# CD_full_schematic.net
KiCad netlist of a schematic drawn in EAGLE
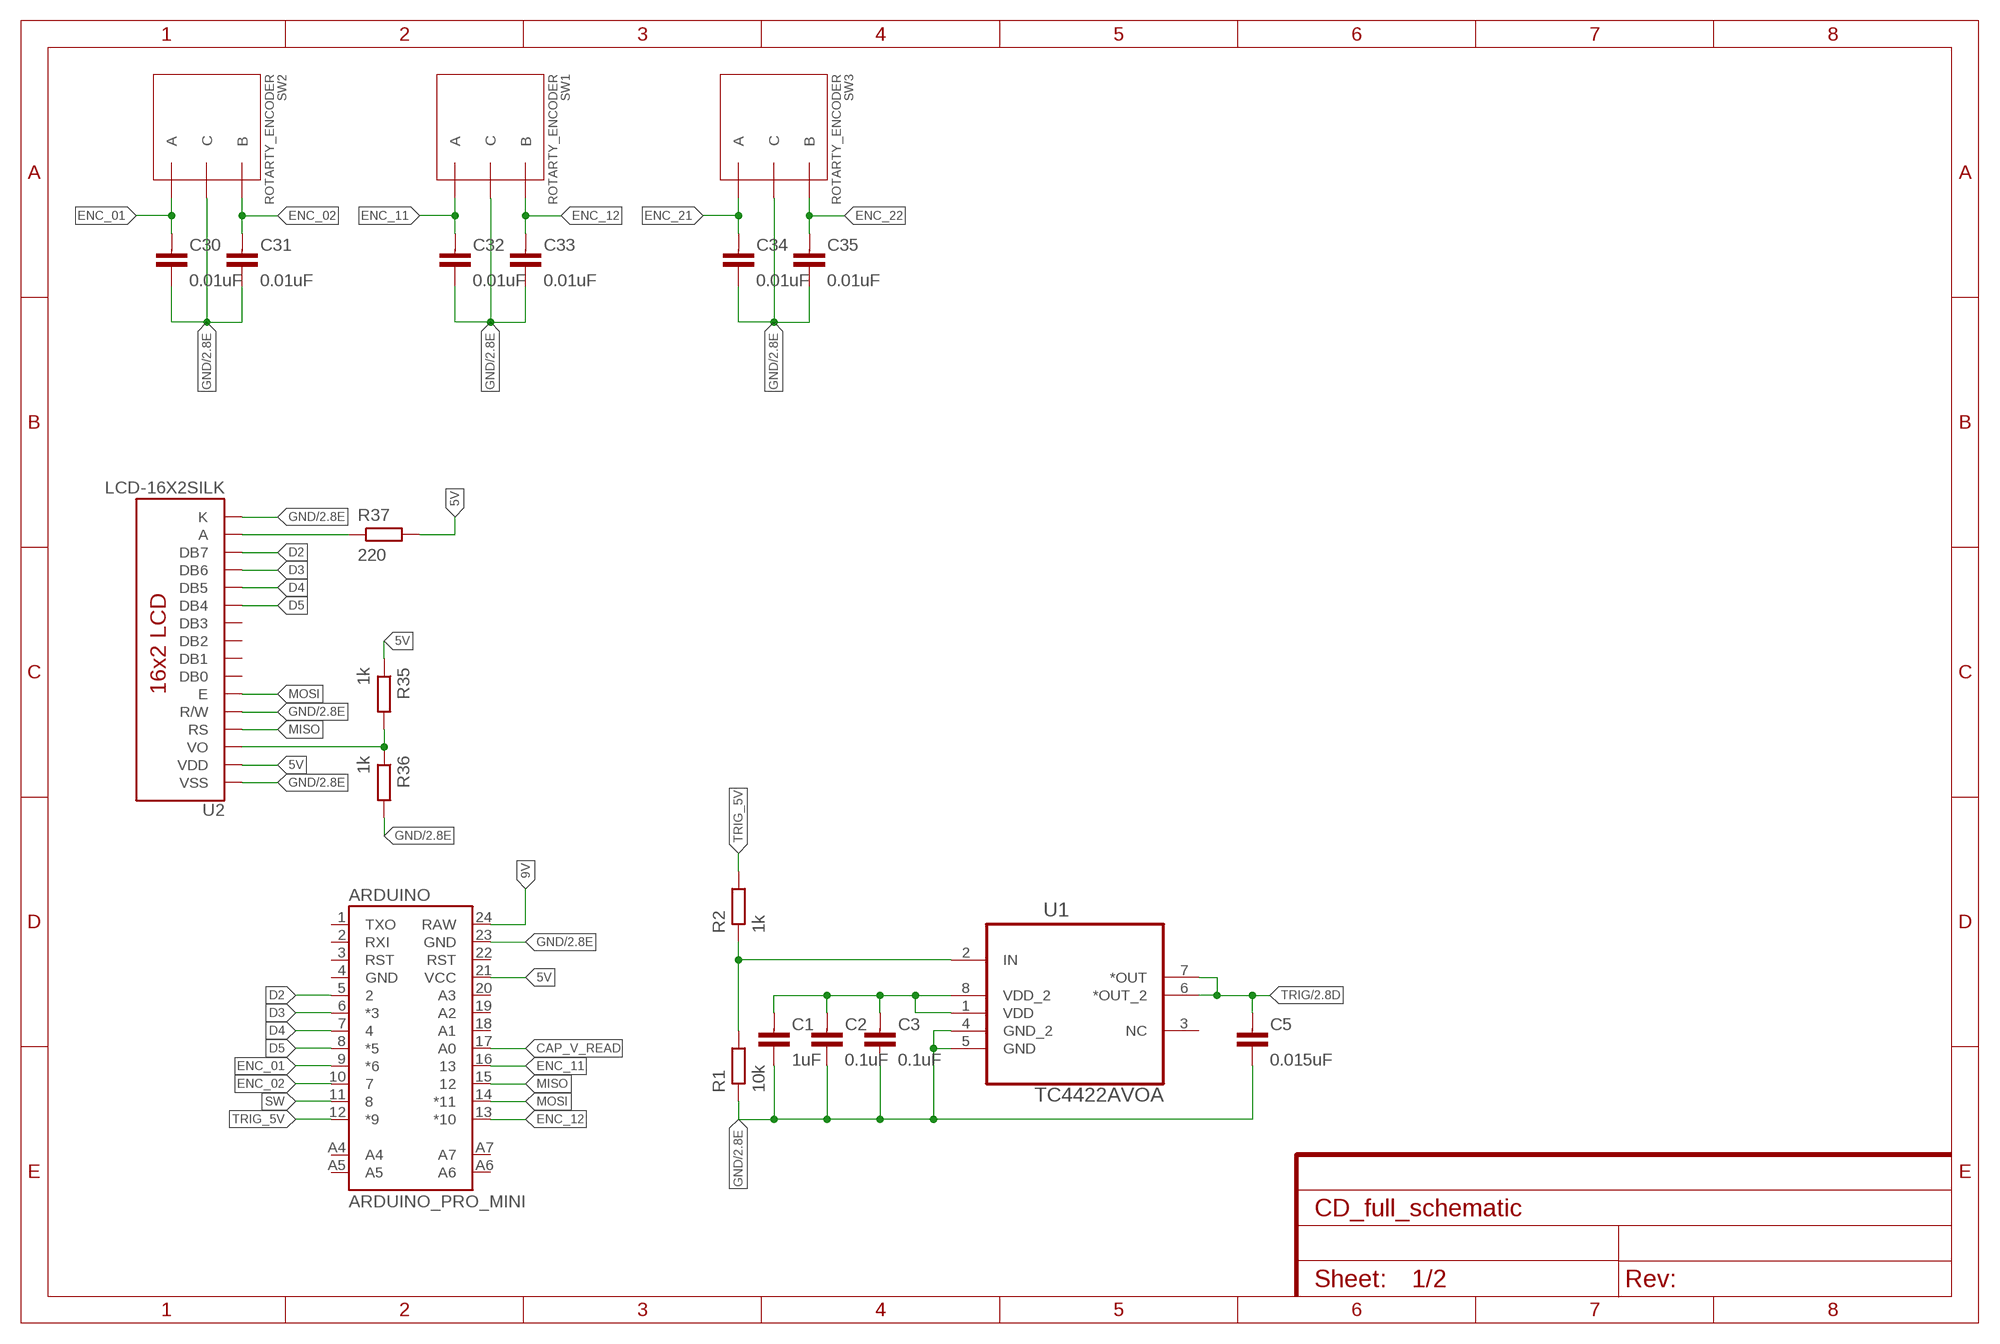
[diagram p0: schematic, sheet 1]
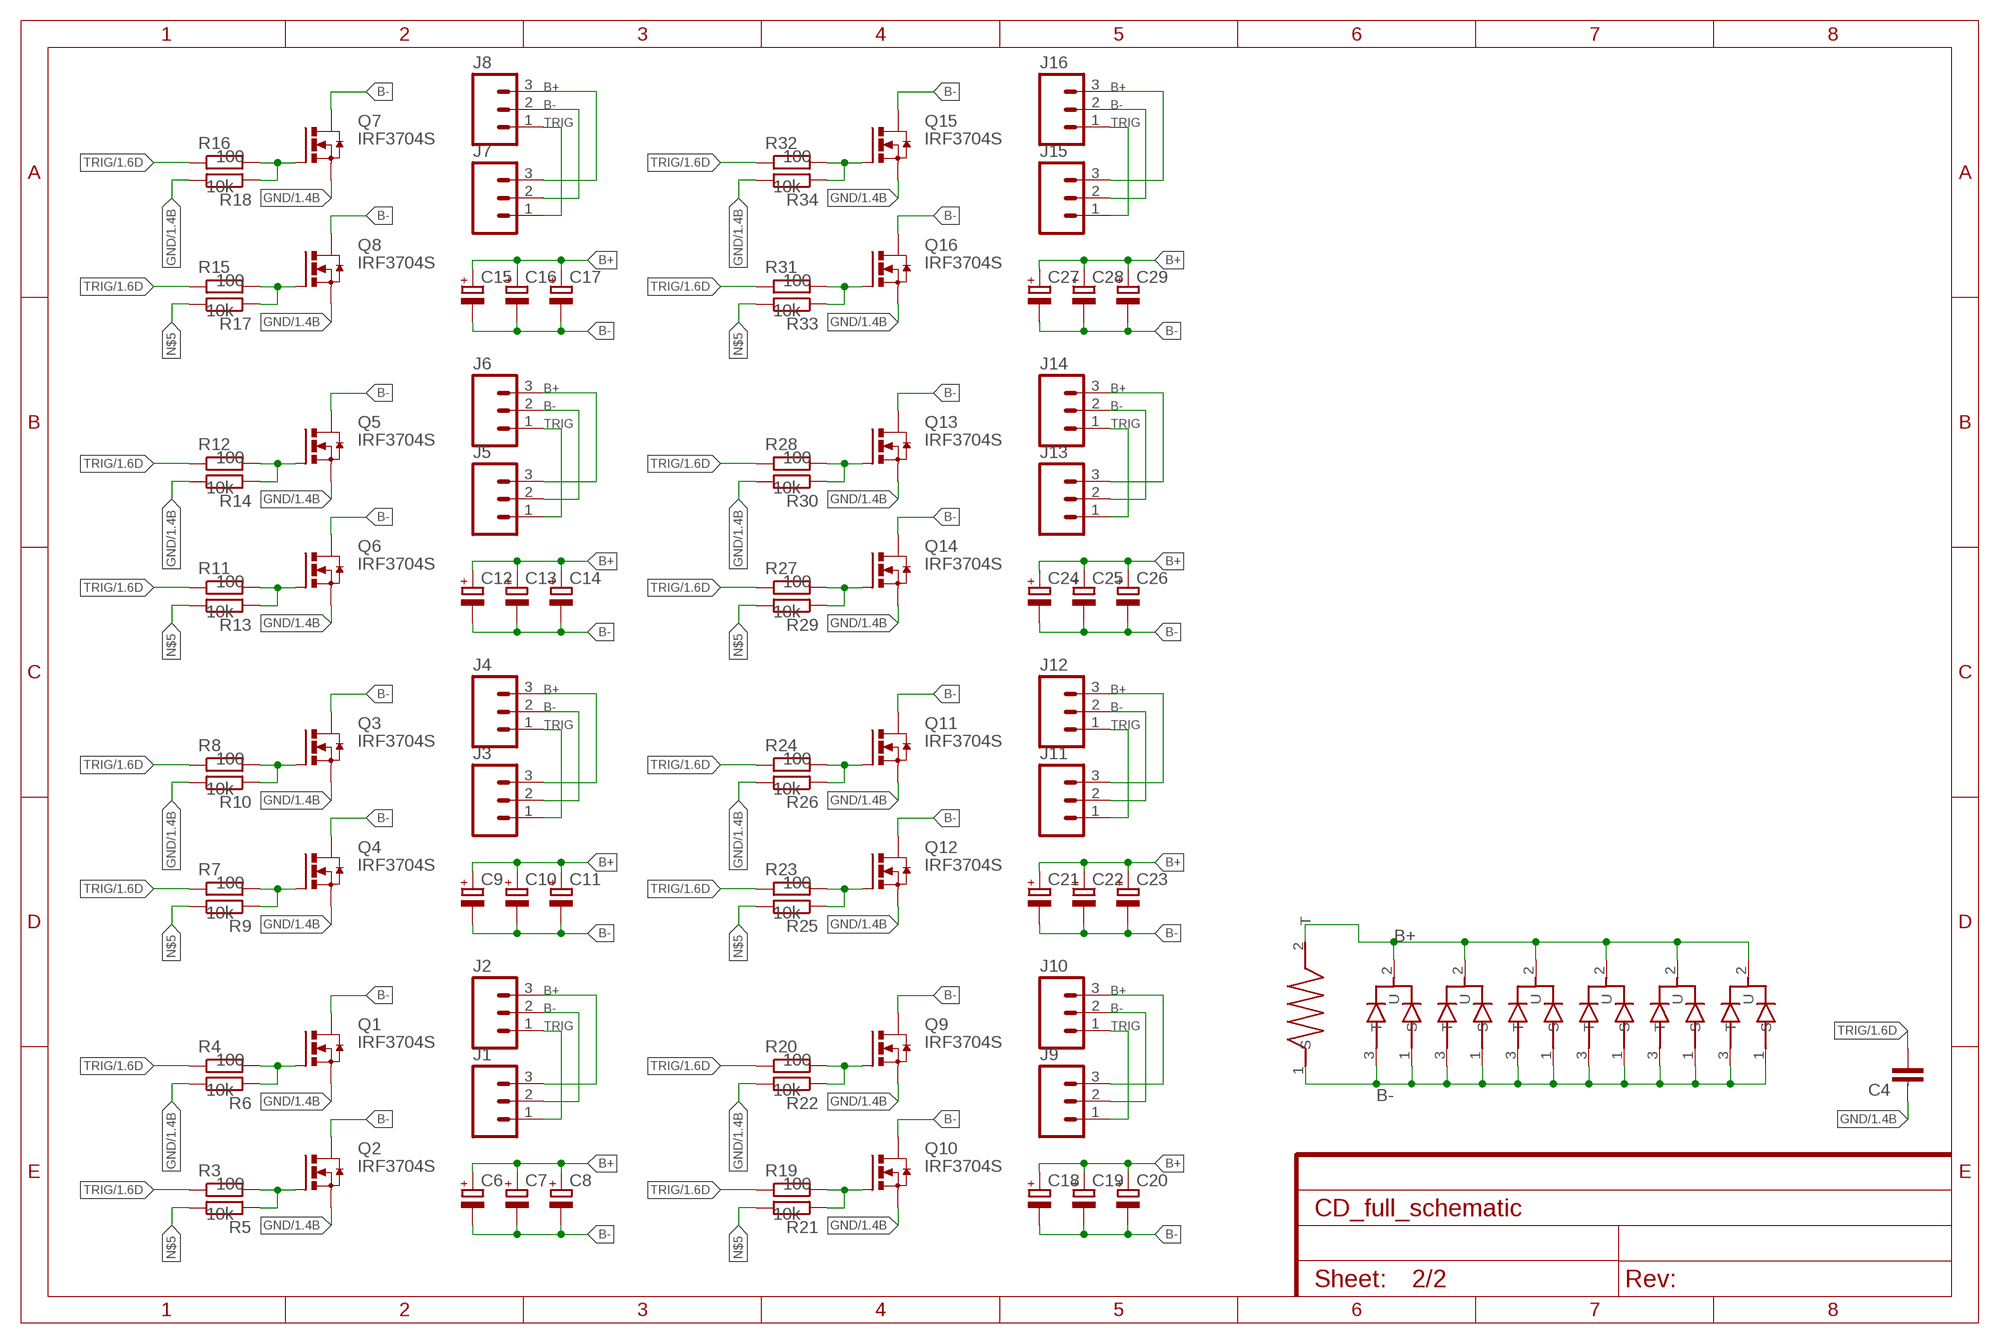
[diagram p1: schematic, sheet 2]

(export (version "E")
  (design (tool "Eeschema 10.0.6"))
  (components
    (comp (ref "ARDUINO")
      (value "ARDUINO_PRO_MINI")
      (footprint "eagle-import:ARDUINO_PRO_MINI")
      (libsource (lib "eagle-import") (part "ARDUINO_PRO_MINI"))
    )
    (comp (ref "C1")
      (value "1uF")
      (footprint "eagle-import:C0805-N")
      (libsource (lib "eagle-import") (part "CAPACITOR0805-N"))
    )
    (comp (ref "C2")
      (value "0.1uF")
      (footprint "eagle-import:C0603-N")
      (libsource (lib "eagle-import") (part "CAPACITOR0603-N"))
    )
    (comp (ref "C3")
      (value "0.1uF")
      (footprint "eagle-import:C0603-N")
      (libsource (lib "eagle-import") (part "CAPACITOR0603-N"))
    )
    (comp (ref "C5")
      (value "0.015uF")
      (footprint "eagle-import:C0603-N")
      (libsource (lib "eagle-import") (part "CAPACITOR0603-N"))
    )
    (comp (ref "C30")
      (value "0.01uF")
      (footprint "eagle-import:C0603-N")
      (libsource (lib "eagle-import") (part "CAPACITOR0603-N"))
    )
    (comp (ref "C31")
      (value "0.01uF")
      (footprint "eagle-import:C0603-N")
      (libsource (lib "eagle-import") (part "CAPACITOR0603-N"))
    )
    (comp (ref "C32")
      (value "0.01uF")
      (footprint "eagle-import:C0603-N")
      (libsource (lib "eagle-import") (part "CAPACITOR0603-N"))
    )
    (comp (ref "C33")
      (value "0.01uF")
      (footprint "eagle-import:C0603-N")
      (libsource (lib "eagle-import") (part "CAPACITOR0603-N"))
    )
    (comp (ref "C34")
      (value "0.01uF")
      (footprint "eagle-import:C0603-N")
      (libsource (lib "eagle-import") (part "CAPACITOR0603-N"))
    )
    (comp (ref "C35")
      (value "0.01uF")
      (footprint "eagle-import:C0603-N")
      (libsource (lib "eagle-import") (part "CAPACITOR0603-N"))
    )
    (comp (ref "R1")
      (value "10k")
      (footprint "eagle-import:R0603-N")
      (libsource (lib "eagle-import") (part "RESISTOR0603-N"))
    )
    (comp (ref "R2")
      (value "1k")
      (footprint "eagle-import:R0603-N")
      (libsource (lib "eagle-import") (part "RESISTOR0603-N"))
    )
    (comp (ref "R35")
      (value "1k")
      (footprint "eagle-import:R0603-N")
      (libsource (lib "eagle-import") (part "RESISTOR0603-N"))
    )
    (comp (ref "R36")
      (value "1k")
      (footprint "eagle-import:R0603-N")
      (libsource (lib "eagle-import") (part "RESISTOR0603-N"))
    )
    (comp (ref "R37")
      (value "220")
      (footprint "eagle-import:R0603-N")
      (libsource (lib "eagle-import") (part "RESISTOR0603-N"))
    )
    (comp (ref "SW1")
      (value "ROTARTY_ENCODER")
      (footprint "eagle-import:ROTARY_ENC_PLAIN")
      (libsource (lib "eagle-import") (part "ROTARTY_ENCODER"))
    )
    (comp (ref "SW2")
      (value "ROTARTY_ENCODER")
      (footprint "eagle-import:ROTARY_ENC_PLAIN")
      (libsource (lib "eagle-import") (part "ROTARTY_ENCODER"))
    )
    (comp (ref "SW3")
      (value "ROTARTY_ENCODER")
      (footprint "eagle-import:ROTARY_ENC_PLAIN")
      (libsource (lib "eagle-import") (part "ROTARTY_ENCODER"))
    )
    (comp (ref "U1")
      (value "TC4422AVOA")
      (footprint "eagle-import:SOIC127P600X175-8N")
      (libsource (lib "eagle-import") (part "TC4422AVOA"))
    )
    (comp (ref "U2")
      (value "LCD-16X2SILK")
      (footprint "eagle-import:LCD-16X2")
      (libsource (lib "eagle-import") (part "LCD-16X2SILK"))
    )
    (comp (ref "C4")
      (value "CAPACITOR0603-N")
      (footprint "eagle-import:C0603-N")
      (libsource (lib "eagle-import") (part "CAPACITOR0603-N"))
    )
    (comp (ref "C6")
      (value "CPOL-EUE10-35")
      (footprint "eagle-import:EB35D")
      (libsource (lib "eagle-import") (part "CPOL-EUE10-35"))
    )
    (comp (ref "C7")
      (value "CPOL-EUE10-35")
      (footprint "eagle-import:EB35D")
      (libsource (lib "eagle-import") (part "CPOL-EUE10-35"))
    )
    (comp (ref "C8")
      (value "CPOL-EUE10-35")
      (footprint "eagle-import:EB35D")
      (libsource (lib "eagle-import") (part "CPOL-EUE10-35"))
    )
    (comp (ref "C9")
      (value "CPOL-EUE10-35")
      (footprint "eagle-import:EB35D")
      (libsource (lib "eagle-import") (part "CPOL-EUE10-35"))
    )
    (comp (ref "C10")
      (value "CPOL-EUE10-35")
      (footprint "eagle-import:EB35D")
      (libsource (lib "eagle-import") (part "CPOL-EUE10-35"))
    )
    (comp (ref "C11")
      (value "CPOL-EUE10-35")
      (footprint "eagle-import:EB35D")
      (libsource (lib "eagle-import") (part "CPOL-EUE10-35"))
    )
    (comp (ref "C12")
      (value "CPOL-EUE10-35")
      (footprint "eagle-import:EB35D")
      (libsource (lib "eagle-import") (part "CPOL-EUE10-35"))
    )
    (comp (ref "C13")
      (value "CPOL-EUE10-35")
      (footprint "eagle-import:EB35D")
      (libsource (lib "eagle-import") (part "CPOL-EUE10-35"))
    )
    (comp (ref "C14")
      (value "CPOL-EUE10-35")
      (footprint "eagle-import:EB35D")
      (libsource (lib "eagle-import") (part "CPOL-EUE10-35"))
    )
    (comp (ref "C15")
      (value "CPOL-EUE10-35")
      (footprint "eagle-import:EB35D")
      (libsource (lib "eagle-import") (part "CPOL-EUE10-35"))
    )
    (comp (ref "C16")
      (value "CPOL-EUE10-35")
      (footprint "eagle-import:EB35D")
      (libsource (lib "eagle-import") (part "CPOL-EUE10-35"))
    )
    (comp (ref "C17")
      (value "CPOL-EUE10-35")
      (footprint "eagle-import:EB35D")
      (libsource (lib "eagle-import") (part "CPOL-EUE10-35"))
    )
    (comp (ref "C18")
      (value "CPOL-EUE10-35")
      (footprint "eagle-import:EB35D")
      (libsource (lib "eagle-import") (part "CPOL-EUE10-35"))
    )
    (comp (ref "C19")
      (value "CPOL-EUE10-35")
      (footprint "eagle-import:EB35D")
      (libsource (lib "eagle-import") (part "CPOL-EUE10-35"))
    )
    (comp (ref "C20")
      (value "CPOL-EUE10-35")
      (footprint "eagle-import:EB35D")
      (libsource (lib "eagle-import") (part "CPOL-EUE10-35"))
    )
    (comp (ref "C21")
      (value "CPOL-EUE10-35")
      (footprint "eagle-import:EB35D")
      (libsource (lib "eagle-import") (part "CPOL-EUE10-35"))
    )
    (comp (ref "C22")
      (value "CPOL-EUE10-35")
      (footprint "eagle-import:EB35D")
      (libsource (lib "eagle-import") (part "CPOL-EUE10-35"))
    )
    (comp (ref "C23")
      (value "CPOL-EUE10-35")
      (footprint "eagle-import:EB35D")
      (libsource (lib "eagle-import") (part "CPOL-EUE10-35"))
    )
    (comp (ref "C24")
      (value "CPOL-EUE10-35")
      (footprint "eagle-import:EB35D")
      (libsource (lib "eagle-import") (part "CPOL-EUE10-35"))
    )
    (comp (ref "C25")
      (value "CPOL-EUE10-35")
      (footprint "eagle-import:EB35D")
      (libsource (lib "eagle-import") (part "CPOL-EUE10-35"))
    )
    (comp (ref "C26")
      (value "CPOL-EUE10-35")
      (footprint "eagle-import:EB35D")
      (libsource (lib "eagle-import") (part "CPOL-EUE10-35"))
    )
    (comp (ref "C27")
      (value "CPOL-EUE10-35")
      (footprint "eagle-import:EB35D")
      (libsource (lib "eagle-import") (part "CPOL-EUE10-35"))
    )
    (comp (ref "C28")
      (value "CPOL-EUE10-35")
      (footprint "eagle-import:EB35D")
      (libsource (lib "eagle-import") (part "CPOL-EUE10-35"))
    )
    (comp (ref "C29")
      (value "CPOL-EUE10-35")
      (footprint "eagle-import:EB35D")
      (libsource (lib "eagle-import") (part "CPOL-EUE10-35"))
    )
    (comp (ref "J1")
      (value "M03PTH")
      (footprint "eagle-import:1X03")
      (libsource (lib "eagle-import") (part "M03PTH"))
    )
    (comp (ref "J2")
      (value "M03PTH")
      (footprint "eagle-import:1X03")
      (libsource (lib "eagle-import") (part "M03PTH"))
    )
    (comp (ref "J3")
      (value "M03PTH")
      (footprint "eagle-import:1X03")
      (libsource (lib "eagle-import") (part "M03PTH"))
    )
    (comp (ref "J4")
      (value "M03PTH")
      (footprint "eagle-import:1X03")
      (libsource (lib "eagle-import") (part "M03PTH"))
    )
    (comp (ref "J5")
      (value "M03PTH")
      (footprint "eagle-import:1X03")
      (libsource (lib "eagle-import") (part "M03PTH"))
    )
    (comp (ref "J6")
      (value "M03PTH")
      (footprint "eagle-import:1X03")
      (libsource (lib "eagle-import") (part "M03PTH"))
    )
    (comp (ref "J7")
      (value "M03PTH")
      (footprint "eagle-import:1X03")
      (libsource (lib "eagle-import") (part "M03PTH"))
    )
    (comp (ref "J8")
      (value "M03PTH")
      (footprint "eagle-import:1X03")
      (libsource (lib "eagle-import") (part "M03PTH"))
    )
    (comp (ref "J9")
      (value "M03PTH")
      (footprint "eagle-import:1X03")
      (libsource (lib "eagle-import") (part "M03PTH"))
    )
    (comp (ref "J10")
      (value "M03PTH")
      (footprint "eagle-import:1X03")
      (libsource (lib "eagle-import") (part "M03PTH"))
    )
    (comp (ref "J11")
      (value "M03PTH")
      (footprint "eagle-import:1X03")
      (libsource (lib "eagle-import") (part "M03PTH"))
    )
    (comp (ref "J12")
      (value "M03PTH")
      (footprint "eagle-import:1X03")
      (libsource (lib "eagle-import") (part "M03PTH"))
    )
    (comp (ref "J13")
      (value "M03PTH")
      (footprint "eagle-import:1X03")
      (libsource (lib "eagle-import") (part "M03PTH"))
    )
    (comp (ref "J14")
      (value "M03PTH")
      (footprint "eagle-import:1X03")
      (libsource (lib "eagle-import") (part "M03PTH"))
    )
    (comp (ref "J15")
      (value "M03PTH")
      (footprint "eagle-import:1X03")
      (libsource (lib "eagle-import") (part "M03PTH"))
    )
    (comp (ref "J16")
      (value "M03PTH")
      (footprint "eagle-import:1X03")
      (libsource (lib "eagle-import") (part "M03PTH"))
    )
    (comp (ref "Q1")
      (value "IRF3704S")
      (footprint "eagle-import:D2PACK")
      (libsource (lib "eagle-import") (part "IRF3704S"))
    )
    (comp (ref "Q2")
      (value "IRF3704S")
      (footprint "eagle-import:D2PACK")
      (libsource (lib "eagle-import") (part "IRF3704S"))
    )
    (comp (ref "Q3")
      (value "IRF3704S")
      (footprint "eagle-import:D2PACK")
      (libsource (lib "eagle-import") (part "IRF3704S"))
    )
    (comp (ref "Q4")
      (value "IRF3704S")
      (footprint "eagle-import:D2PACK")
      (libsource (lib "eagle-import") (part "IRF3704S"))
    )
    (comp (ref "Q5")
      (value "IRF3704S")
      (footprint "eagle-import:D2PACK")
      (libsource (lib "eagle-import") (part "IRF3704S"))
    )
    (comp (ref "Q6")
      (value "IRF3704S")
      (footprint "eagle-import:D2PACK")
      (libsource (lib "eagle-import") (part "IRF3704S"))
    )
    (comp (ref "Q7")
      (value "IRF3704S")
      (footprint "eagle-import:D2PACK")
      (libsource (lib "eagle-import") (part "IRF3704S"))
    )
    (comp (ref "Q8")
      (value "IRF3704S")
      (footprint "eagle-import:D2PACK")
      (libsource (lib "eagle-import") (part "IRF3704S"))
    )
    (comp (ref "Q9")
      (value "IRF3704S")
      (footprint "eagle-import:D2PACK")
      (libsource (lib "eagle-import") (part "IRF3704S"))
    )
    (comp (ref "Q10")
      (value "IRF3704S")
      (footprint "eagle-import:D2PACK")
      (libsource (lib "eagle-import") (part "IRF3704S"))
    )
    (comp (ref "Q11")
      (value "IRF3704S")
      (footprint "eagle-import:D2PACK")
      (libsource (lib "eagle-import") (part "IRF3704S"))
    )
    (comp (ref "Q12")
      (value "IRF3704S")
      (footprint "eagle-import:D2PACK")
      (libsource (lib "eagle-import") (part "IRF3704S"))
    )
    (comp (ref "Q13")
      (value "IRF3704S")
      (footprint "eagle-import:D2PACK")
      (libsource (lib "eagle-import") (part "IRF3704S"))
    )
    (comp (ref "Q14")
      (value "IRF3704S")
      (footprint "eagle-import:D2PACK")
      (libsource (lib "eagle-import") (part "IRF3704S"))
    )
    (comp (ref "Q15")
      (value "IRF3704S")
      (footprint "eagle-import:D2PACK")
      (libsource (lib "eagle-import") (part "IRF3704S"))
    )
    (comp (ref "Q16")
      (value "IRF3704S")
      (footprint "eagle-import:D2PACK")
      (libsource (lib "eagle-import") (part "IRF3704S"))
    )
    (comp (ref "R3")
      (value "100")
      (footprint "eagle-import:R0603-N")
      (libsource (lib "eagle-import") (part "RESISTOR0603-N"))
    )
    (comp (ref "R4")
      (value "100")
      (footprint "eagle-import:R0603-N")
      (libsource (lib "eagle-import") (part "RESISTOR0603-N"))
    )
    (comp (ref "R5")
      (value "10k")
      (footprint "eagle-import:R0603-N")
      (libsource (lib "eagle-import") (part "RESISTOR0603-N"))
    )
    (comp (ref "R6")
      (value "10k")
      (footprint "eagle-import:R0603-N")
      (libsource (lib "eagle-import") (part "RESISTOR0603-N"))
    )
    (comp (ref "R7")
      (value "100")
      (footprint "eagle-import:R0603-N")
      (libsource (lib "eagle-import") (part "RESISTOR0603-N"))
    )
    (comp (ref "R8")
      (value "100")
      (footprint "eagle-import:R0603-N")
      (libsource (lib "eagle-import") (part "RESISTOR0603-N"))
    )
    (comp (ref "R9")
      (value "10k")
      (footprint "eagle-import:R0603-N")
      (libsource (lib "eagle-import") (part "RESISTOR0603-N"))
    )
    (comp (ref "R10")
      (value "10k")
      (footprint "eagle-import:R0603-N")
      (libsource (lib "eagle-import") (part "RESISTOR0603-N"))
    )
    (comp (ref "R11")
      (value "100")
      (footprint "eagle-import:R0603-N")
      (libsource (lib "eagle-import") (part "RESISTOR0603-N"))
    )
    (comp (ref "R12")
      (value "100")
      (footprint "eagle-import:R0603-N")
      (libsource (lib "eagle-import") (part "RESISTOR0603-N"))
    )
    (comp (ref "R13")
      (value "10k")
      (footprint "eagle-import:R0603-N")
      (libsource (lib "eagle-import") (part "RESISTOR0603-N"))
    )
    (comp (ref "R14")
      (value "10k")
      (footprint "eagle-import:R0603-N")
      (libsource (lib "eagle-import") (part "RESISTOR0603-N"))
    )
    (comp (ref "R15")
      (value "100")
      (footprint "eagle-import:R0603-N")
      (libsource (lib "eagle-import") (part "RESISTOR0603-N"))
    )
    (comp (ref "R16")
      (value "100")
      (footprint "eagle-import:R0603-N")
      (libsource (lib "eagle-import") (part "RESISTOR0603-N"))
    )
    (comp (ref "R17")
      (value "10k")
      (footprint "eagle-import:R0603-N")
      (libsource (lib "eagle-import") (part "RESISTOR0603-N"))
    )
    (comp (ref "R18")
      (value "10k")
      (footprint "eagle-import:R0603-N")
      (libsource (lib "eagle-import") (part "RESISTOR0603-N"))
    )
    (comp (ref "R19")
      (value "100")
      (footprint "eagle-import:R0603-N")
      (libsource (lib "eagle-import") (part "RESISTOR0603-N"))
    )
    (comp (ref "R20")
      (value "100")
      (footprint "eagle-import:R0603-N")
      (libsource (lib "eagle-import") (part "RESISTOR0603-N"))
    )
    (comp (ref "R21")
      (value "10k")
      (footprint "eagle-import:R0603-N")
      (libsource (lib "eagle-import") (part "RESISTOR0603-N"))
    )
    (comp (ref "R22")
      (value "10k")
      (footprint "eagle-import:R0603-N")
      (libsource (lib "eagle-import") (part "RESISTOR0603-N"))
    )
    (comp (ref "R23")
      (value "100")
      (footprint "eagle-import:R0603-N")
      (libsource (lib "eagle-import") (part "RESISTOR0603-N"))
    )
    (comp (ref "R24")
      (value "100")
      (footprint "eagle-import:R0603-N")
      (libsource (lib "eagle-import") (part "RESISTOR0603-N"))
    )
    (comp (ref "R25")
      (value "10k")
      (footprint "eagle-import:R0603-N")
      (libsource (lib "eagle-import") (part "RESISTOR0603-N"))
    )
    (comp (ref "R26")
      (value "10k")
      (footprint "eagle-import:R0603-N")
      (libsource (lib "eagle-import") (part "RESISTOR0603-N"))
    )
    (comp (ref "R27")
      (value "100")
      (footprint "eagle-import:R0603-N")
      (libsource (lib "eagle-import") (part "RESISTOR0603-N"))
    )
    (comp (ref "R28")
      (value "100")
      (footprint "eagle-import:R0603-N")
      (libsource (lib "eagle-import") (part "RESISTOR0603-N"))
    )
    (comp (ref "R29")
      (value "10k")
      (footprint "eagle-import:R0603-N")
      (libsource (lib "eagle-import") (part "RESISTOR0603-N"))
    )
    (comp (ref "R30")
      (value "10k")
      (footprint "eagle-import:R0603-N")
      (libsource (lib "eagle-import") (part "RESISTOR0603-N"))
    )
    (comp (ref "R31")
      (value "100")
      (footprint "eagle-import:R0603-N")
      (libsource (lib "eagle-import") (part "RESISTOR0603-N"))
    )
    (comp (ref "R32")
      (value "100")
      (footprint "eagle-import:R0603-N")
      (libsource (lib "eagle-import") (part "RESISTOR0603-N"))
    )
    (comp (ref "R33")
      (value "10k")
      (footprint "eagle-import:R0603-N")
      (libsource (lib "eagle-import") (part "RESISTOR0603-N"))
    )
    (comp (ref "R34")
      (value "10k")
      (footprint "eagle-import:R0603-N")
      (libsource (lib "eagle-import") (part "RESISTOR0603-N"))
    )
    (comp (ref "U$1")
      (value "STTH6002CW")
      (footprint "eagle-import:TO-247")
      (libsource (lib "eagle-import") (part "STTH6002CW"))
    )
    (comp (ref "U$2")
      (value "STTH6002CW")
      (footprint "eagle-import:TO-247")
      (libsource (lib "eagle-import") (part "STTH6002CW"))
    )
    (comp (ref "U$3")
      (value "STTH6002CW")
      (footprint "eagle-import:TO-247")
      (libsource (lib "eagle-import") (part "STTH6002CW"))
    )
    (comp (ref "U$4")
      (value "STTH6002CW")
      (footprint "eagle-import:TO-247")
      (libsource (lib "eagle-import") (part "STTH6002CW"))
    )
    (comp (ref "U$5")
      (value "STTH6002CW")
      (footprint "eagle-import:TO-247")
      (libsource (lib "eagle-import") (part "STTH6002CW"))
    )
    (comp (ref "U$6")
      (value "STTH6002CW")
      (footprint "eagle-import:TO-247")
      (libsource (lib "eagle-import") (part "STTH6002CW"))
    )
    (comp (ref "U$7")
      (value "RESISTOR_5W_1INCH")
      (footprint "eagle-import:RESISTOR_1INCH_5W")
      (libsource (lib "eagle-import") (part "RESISTOR_5W_1INCH"))
    )
  )
  (nets
    (net (code "1") (name "5V") (class "Default")
      (node (ref "ARDUINO") (pin "21") (pinfunction "VCC_21") (pintype "bidirectional"))
      (node (ref "R35") (pin "1") (pinfunction "P$1_1") (pintype "passive"))
      (node (ref "R37") (pin "2") (pinfunction "P$2_2") (pintype "passive"))
      (node (ref "U2") (pin "2") (pinfunction "VDD_2") (pintype "power_in"))
    )
    (net (code "2") (name "9V") (class "Default")
      (node (ref "ARDUINO") (pin "24") (pinfunction "RAW_24") (pintype "bidirectional"))
    )
    (net (code "3") (name "B+") (class "Default")
      (node (ref "C10") (pin "+") (pinfunction "+_+") (pintype "passive"))
      (node (ref "C11") (pin "+") (pinfunction "+_+") (pintype "passive"))
      (node (ref "C12") (pin "+") (pinfunction "+_+") (pintype "passive"))
      (node (ref "C13") (pin "+") (pinfunction "+_+") (pintype "passive"))
      (node (ref "C14") (pin "+") (pinfunction "+_+") (pintype "passive"))
      (node (ref "C15") (pin "+") (pinfunction "+_+") (pintype "passive"))
      (node (ref "C16") (pin "+") (pinfunction "+_+") (pintype "passive"))
      (node (ref "C17") (pin "+") (pinfunction "+_+") (pintype "passive"))
      (node (ref "C18") (pin "+") (pinfunction "+_+") (pintype "passive"))
      (node (ref "C19") (pin "+") (pinfunction "+_+") (pintype "passive"))
      (node (ref "C20") (pin "+") (pinfunction "+_+") (pintype "passive"))
      (node (ref "C21") (pin "+") (pinfunction "+_+") (pintype "passive"))
      (node (ref "C22") (pin "+") (pinfunction "+_+") (pintype "passive"))
      (node (ref "C23") (pin "+") (pinfunction "+_+") (pintype "passive"))
      (node (ref "C24") (pin "+") (pinfunction "+_+") (pintype "passive"))
      (node (ref "C25") (pin "+") (pinfunction "+_+") (pintype "passive"))
      (node (ref "C26") (pin "+") (pinfunction "+_+") (pintype "passive"))
      (node (ref "C27") (pin "+") (pinfunction "+_+") (pintype "passive"))
      (node (ref "C28") (pin "+") (pinfunction "+_+") (pintype "passive"))
      (node (ref "C29") (pin "+") (pinfunction "+_+") (pintype "passive"))
      (node (ref "C6") (pin "+") (pinfunction "+_+") (pintype "passive"))
      (node (ref "C7") (pin "+") (pinfunction "+_+") (pintype "passive"))
      (node (ref "C8") (pin "+") (pinfunction "+_+") (pintype "passive"))
      (node (ref "C9") (pin "+") (pinfunction "+_+") (pintype "passive"))
      (node (ref "J1") (pin "3") (pinfunction "3_3") (pintype "passive"))
      (node (ref "J10") (pin "3") (pinfunction "3_3") (pintype "passive"))
      (node (ref "J11") (pin "3") (pinfunction "3_3") (pintype "passive"))
      (node (ref "J12") (pin "3") (pinfunction "3_3") (pintype "passive"))
      (node (ref "J13") (pin "3") (pinfunction "3_3") (pintype "passive"))
      (node (ref "J14") (pin "3") (pinfunction "3_3") (pintype "passive"))
      (node (ref "J15") (pin "3") (pinfunction "3_3") (pintype "passive"))
      (node (ref "J16") (pin "3") (pinfunction "3_3") (pintype "passive"))
      (node (ref "J2") (pin "3") (pinfunction "3_3") (pintype "passive"))
      (node (ref "J3") (pin "3") (pinfunction "3_3") (pintype "passive"))
      (node (ref "J4") (pin "3") (pinfunction "3_3") (pintype "passive"))
      (node (ref "J5") (pin "3") (pinfunction "3_3") (pintype "passive"))
      (node (ref "J6") (pin "3") (pinfunction "3_3") (pintype "passive"))
      (node (ref "J7") (pin "3") (pinfunction "3_3") (pintype "passive"))
      (node (ref "J8") (pin "3") (pinfunction "3_3") (pintype "passive"))
      (node (ref "J9") (pin "3") (pinfunction "3_3") (pintype "passive"))
      (node (ref "U$1") (pin "2") (pinfunction "U_2") (pintype "bidirectional"))
      (node (ref "U$2") (pin "2") (pinfunction "U_2") (pintype "bidirectional"))
      (node (ref "U$3") (pin "2") (pinfunction "U_2") (pintype "bidirectional"))
      (node (ref "U$4") (pin "2") (pinfunction "U_2") (pintype "bidirectional"))
      (node (ref "U$5") (pin "2") (pinfunction "U_2") (pintype "bidirectional"))
      (node (ref "U$6") (pin "2") (pinfunction "U_2") (pintype "bidirectional"))
      (node (ref "U$7") (pin "2") (pinfunction "T_2") (pintype "bidirectional"))
    )
    (net (code "4") (name "B-") (class "Default")
      (node (ref "C10") (pin "-") (pinfunction "-_-") (pintype "passive"))
      (node (ref "C11") (pin "-") (pinfunction "-_-") (pintype "passive"))
      (node (ref "C12") (pin "-") (pinfunction "-_-") (pintype "passive"))
      (node (ref "C13") (pin "-") (pinfunction "-_-") (pintype "passive"))
      (node (ref "C14") (pin "-") (pinfunction "-_-") (pintype "passive"))
      (node (ref "C15") (pin "-") (pinfunction "-_-") (pintype "passive"))
      (node (ref "C16") (pin "-") (pinfunction "-_-") (pintype "passive"))
      (node (ref "C17") (pin "-") (pinfunction "-_-") (pintype "passive"))
      (node (ref "C18") (pin "-") (pinfunction "-_-") (pintype "passive"))
      (node (ref "C19") (pin "-") (pinfunction "-_-") (pintype "passive"))
      (node (ref "C20") (pin "-") (pinfunction "-_-") (pintype "passive"))
      (node (ref "C21") (pin "-") (pinfunction "-_-") (pintype "passive"))
      (node (ref "C22") (pin "-") (pinfunction "-_-") (pintype "passive"))
      (node (ref "C23") (pin "-") (pinfunction "-_-") (pintype "passive"))
      (node (ref "C24") (pin "-") (pinfunction "-_-") (pintype "passive"))
      (node (ref "C25") (pin "-") (pinfunction "-_-") (pintype "passive"))
      (node (ref "C26") (pin "-") (pinfunction "-_-") (pintype "passive"))
      (node (ref "C27") (pin "-") (pinfunction "-_-") (pintype "passive"))
      (node (ref "C28") (pin "-") (pinfunction "-_-") (pintype "passive"))
      (node (ref "C29") (pin "-") (pinfunction "-_-") (pintype "passive"))
      (node (ref "C6") (pin "-") (pinfunction "-_-") (pintype "passive"))
      (node (ref "C7") (pin "-") (pinfunction "-_-") (pintype "passive"))
      (node (ref "C8") (pin "-") (pinfunction "-_-") (pintype "passive"))
      (node (ref "C9") (pin "-") (pinfunction "-_-") (pintype "passive"))
      (node (ref "J1") (pin "2") (pinfunction "2_2") (pintype "passive"))
      (node (ref "J10") (pin "2") (pinfunction "2_2") (pintype "passive"))
      (node (ref "J11") (pin "2") (pinfunction "2_2") (pintype "passive"))
      (node (ref "J12") (pin "2") (pinfunction "2_2") (pintype "passive"))
      (node (ref "J13") (pin "2") (pinfunction "2_2") (pintype "passive"))
      (node (ref "J14") (pin "2") (pinfunction "2_2") (pintype "passive"))
      (node (ref "J15") (pin "2") (pinfunction "2_2") (pintype "passive"))
      (node (ref "J16") (pin "2") (pinfunction "2_2") (pintype "passive"))
      (node (ref "J2") (pin "2") (pinfunction "2_2") (pintype "passive"))
      (node (ref "J3") (pin "2") (pinfunction "2_2") (pintype "passive"))
      (node (ref "J4") (pin "2") (pinfunction "2_2") (pintype "passive"))
      (node (ref "J5") (pin "2") (pinfunction "2_2") (pintype "passive"))
      (node (ref "J6") (pin "2") (pinfunction "2_2") (pintype "passive"))
      (node (ref "J7") (pin "2") (pinfunction "2_2") (pintype "passive"))
      (node (ref "J8") (pin "2") (pinfunction "2_2") (pintype "passive"))
      (node (ref "J9") (pin "2") (pinfunction "2_2") (pintype "passive"))
      (node (ref "Q1") (pin "2") (pinfunction "D_2") (pintype "passive"))
      (node (ref "Q10") (pin "2") (pinfunction "D_2") (pintype "passive"))
      (node (ref "Q11") (pin "2") (pinfunction "D_2") (pintype "passive"))
      (node (ref "Q12") (pin "2") (pinfunction "D_2") (pintype "passive"))
      (node (ref "Q13") (pin "2") (pinfunction "D_2") (pintype "passive"))
      (node (ref "Q14") (pin "2") (pinfunction "D_2") (pintype "passive"))
      (node (ref "Q15") (pin "2") (pinfunction "D_2") (pintype "passive"))
      (node (ref "Q16") (pin "2") (pinfunction "D_2") (pintype "passive"))
      (node (ref "Q2") (pin "2") (pinfunction "D_2") (pintype "passive"))
      (node (ref "Q3") (pin "2") (pinfunction "D_2") (pintype "passive"))
      (node (ref "Q4") (pin "2") (pinfunction "D_2") (pintype "passive"))
      (node (ref "Q5") (pin "2") (pinfunction "D_2") (pintype "passive"))
      (node (ref "Q6") (pin "2") (pinfunction "D_2") (pintype "passive"))
      (node (ref "Q7") (pin "2") (pinfunction "D_2") (pintype "passive"))
      (node (ref "Q8") (pin "2") (pinfunction "D_2") (pintype "passive"))
      (node (ref "Q9") (pin "2") (pinfunction "D_2") (pintype "passive"))
      (node (ref "U$1") (pin "1") (pinfunction "S_1") (pintype "bidirectional"))
      (node (ref "U$1") (pin "3") (pinfunction "T_3") (pintype "bidirectional"))
      (node (ref "U$2") (pin "1") (pinfunction "S_1") (pintype "bidirectional"))
      (node (ref "U$2") (pin "3") (pinfunction "T_3") (pintype "bidirectional"))
      (node (ref "U$3") (pin "1") (pinfunction "S_1") (pintype "bidirectional"))
      (node (ref "U$3") (pin "3") (pinfunction "T_3") (pintype "bidirectional"))
      (node (ref "U$4") (pin "1") (pinfunction "S_1") (pintype "bidirectional"))
      (node (ref "U$4") (pin "3") (pinfunction "T_3") (pintype "bidirectional"))
      (node (ref "U$5") (pin "1") (pinfunction "S_1") (pintype "bidirectional"))
      (node (ref "U$5") (pin "3") (pinfunction "T_3") (pintype "bidirectional"))
      (node (ref "U$6") (pin "1") (pinfunction "S_1") (pintype "bidirectional"))
      (node (ref "U$6") (pin "3") (pinfunction "T_3") (pintype "bidirectional"))
      (node (ref "U$7") (pin "1") (pinfunction "S_1") (pintype "bidirectional"))
    )
    (net (code "5") (name "CAP_V_READ") (class "Default")
      (node (ref "ARDUINO") (pin "17") (pinfunction "A0_17") (pintype "bidirectional"))
    )
    (net (code "6") (name "D2") (class "Default")
      (node (ref "ARDUINO") (pin "5") (pinfunction "2_5") (pintype "bidirectional"))
      (node (ref "U2") (pin "14") (pinfunction "DB7_14") (pintype "bidirectional"))
    )
    (net (code "7") (name "D3") (class "Default")
      (node (ref "ARDUINO") (pin "6") (pinfunction "*3_6") (pintype "bidirectional"))
      (node (ref "U2") (pin "13") (pinfunction "DB6_13") (pintype "bidirectional"))
    )
    (net (code "8") (name "D4") (class "Default")
      (node (ref "ARDUINO") (pin "7") (pinfunction "4_7") (pintype "bidirectional"))
      (node (ref "U2") (pin "12") (pinfunction "DB5_12") (pintype "bidirectional"))
    )
    (net (code "9") (name "D5") (class "Default")
      (node (ref "ARDUINO") (pin "8") (pinfunction "*5_8") (pintype "bidirectional"))
      (node (ref "U2") (pin "11") (pinfunction "DB4_11") (pintype "bidirectional"))
    )
    (net (code "10") (name "ENC_01") (class "Default")
      (node (ref "ARDUINO") (pin "9") (pinfunction "*6_9") (pintype "bidirectional"))
      (node (ref "C30") (pin "1") (pinfunction "1_1") (pintype "passive"))
      (node (ref "SW2") (pin "A") (pinfunction "A_A") (pintype "bidirectional"))
    )
    (net (code "11") (name "ENC_02") (class "Default")
      (node (ref "ARDUINO") (pin "10") (pinfunction "7_10") (pintype "bidirectional"))
      (node (ref "C31") (pin "1") (pinfunction "1_1") (pintype "passive"))
      (node (ref "SW2") (pin "B") (pinfunction "B_B") (pintype "bidirectional"))
    )
    (net (code "12") (name "ENC_11") (class "Default")
      (node (ref "ARDUINO") (pin "16") (pinfunction "13_16") (pintype "bidirectional"))
      (node (ref "C32") (pin "1") (pinfunction "1_1") (pintype "passive"))
      (node (ref "SW1") (pin "A") (pinfunction "A_A") (pintype "bidirectional"))
    )
    (net (code "13") (name "ENC_12") (class "Default")
      (node (ref "ARDUINO") (pin "13") (pinfunction "*10_13") (pintype "bidirectional"))
      (node (ref "C33") (pin "1") (pinfunction "1_1") (pintype "passive"))
      (node (ref "SW1") (pin "B") (pinfunction "B_B") (pintype "bidirectional"))
    )
    (net (code "14") (name "ENC_21") (class "Default")
      (node (ref "C34") (pin "1") (pinfunction "1_1") (pintype "passive"))
      (node (ref "SW3") (pin "A") (pinfunction "A_A") (pintype "bidirectional"))
    )
    (net (code "15") (name "ENC_22") (class "Default")
      (node (ref "C35") (pin "1") (pinfunction "1_1") (pintype "passive"))
      (node (ref "SW3") (pin "B") (pinfunction "B_B") (pintype "bidirectional"))
    )
    (net (code "16") (name "GND") (class "Default")
      (node (ref "ARDUINO") (pin "23") (pinfunction "GND_23") (pintype "bidirectional"))
      (node (ref "C1") (pin "2") (pinfunction "2_2") (pintype "passive"))
      (node (ref "C2") (pin "2") (pinfunction "2_2") (pintype "passive"))
      (node (ref "C3") (pin "2") (pinfunction "2_2") (pintype "passive"))
      (node (ref "C30") (pin "2") (pinfunction "2_2") (pintype "passive"))
      (node (ref "C31") (pin "2") (pinfunction "2_2") (pintype "passive"))
      (node (ref "C32") (pin "2") (pinfunction "2_2") (pintype "passive"))
      (node (ref "C33") (pin "2") (pinfunction "2_2") (pintype "passive"))
      (node (ref "C34") (pin "2") (pinfunction "2_2") (pintype "passive"))
      (node (ref "C35") (pin "2") (pinfunction "2_2") (pintype "passive"))
      (node (ref "C4") (pin "1") (pinfunction "1_1") (pintype "passive"))
      (node (ref "C5") (pin "2") (pinfunction "2_2") (pintype "passive"))
      (node (ref "Q1") (pin "1") (pinfunction "G_1") (pintype "passive"))
      (node (ref "Q1") (pin "3") (pinfunction "S_3") (pintype "passive"))
      (node (ref "Q10") (pin "3") (pinfunction "S_3") (pintype "passive"))
      (node (ref "Q11") (pin "1") (pinfunction "G_1") (pintype "passive"))
      (node (ref "Q11") (pin "3") (pinfunction "S_3") (pintype "passive"))
      (node (ref "Q12") (pin "3") (pinfunction "S_3") (pintype "passive"))
      (node (ref "Q13") (pin "1") (pinfunction "G_1") (pintype "passive"))
      (node (ref "Q13") (pin "3") (pinfunction "S_3") (pintype "passive"))
      (node (ref "Q14") (pin "3") (pinfunction "S_3") (pintype "passive"))
      (node (ref "Q15") (pin "1") (pinfunction "G_1") (pintype "passive"))
      (node (ref "Q15") (pin "3") (pinfunction "S_3") (pintype "passive"))
      (node (ref "Q16") (pin "3") (pinfunction "S_3") (pintype "passive"))
      (node (ref "Q2") (pin "3") (pinfunction "S_3") (pintype "passive"))
      (node (ref "Q3") (pin "1") (pinfunction "G_1") (pintype "passive"))
      (node (ref "Q3") (pin "3") (pinfunction "S_3") (pintype "passive"))
      (node (ref "Q4") (pin "3") (pinfunction "S_3") (pintype "passive"))
      (node (ref "Q5") (pin "1") (pinfunction "G_1") (pintype "passive"))
      (node (ref "Q5") (pin "3") (pinfunction "S_3") (pintype "passive"))
      (node (ref "Q6") (pin "3") (pinfunction "S_3") (pintype "passive"))
      (node (ref "Q7") (pin "1") (pinfunction "G_1") (pintype "passive"))
      (node (ref "Q7") (pin "3") (pinfunction "S_3") (pintype "passive"))
      (node (ref "Q8") (pin "3") (pinfunction "S_3") (pintype "passive"))
      (node (ref "Q9") (pin "1") (pinfunction "G_1") (pintype "passive"))
      (node (ref "Q9") (pin "3") (pinfunction "S_3") (pintype "passive"))
      (node (ref "R1") (pin "1") (pinfunction "P$1_1") (pintype "passive"))
      (node (ref "R10") (pin "1") (pinfunction "P$1_1") (pintype "passive"))
      (node (ref "R10") (pin "2") (pinfunction "P$2_2") (pintype "passive"))
      (node (ref "R12") (pin "2") (pinfunction "P$2_2") (pintype "passive"))
      (node (ref "R14") (pin "1") (pinfunction "P$1_1") (pintype "passive"))
      (node (ref "R14") (pin "2") (pinfunction "P$2_2") (pintype "passive"))
      (node (ref "R16") (pin "2") (pinfunction "P$2_2") (pintype "passive"))
      (node (ref "R18") (pin "1") (pinfunction "P$1_1") (pintype "passive"))
      (node (ref "R18") (pin "2") (pinfunction "P$2_2") (pintype "passive"))
      (node (ref "R20") (pin "2") (pinfunction "P$2_2") (pintype "passive"))
      (node (ref "R22") (pin "1") (pinfunction "P$1_1") (pintype "passive"))
      (node (ref "R22") (pin "2") (pinfunction "P$2_2") (pintype "passive"))
      (node (ref "R24") (pin "2") (pinfunction "P$2_2") (pintype "passive"))
      (node (ref "R26") (pin "1") (pinfunction "P$1_1") (pintype "passive"))
      (node (ref "R26") (pin "2") (pinfunction "P$2_2") (pintype "passive"))
      (node (ref "R28") (pin "2") (pinfunction "P$2_2") (pintype "passive"))
      (node (ref "R30") (pin "1") (pinfunction "P$1_1") (pintype "passive"))
      (node (ref "R30") (pin "2") (pinfunction "P$2_2") (pintype "passive"))
      (node (ref "R32") (pin "2") (pinfunction "P$2_2") (pintype "passive"))
      (node (ref "R34") (pin "1") (pinfunction "P$1_1") (pintype "passive"))
      (node (ref "R34") (pin "2") (pinfunction "P$2_2") (pintype "passive"))
      (node (ref "R36") (pin "2") (pinfunction "P$2_2") (pintype "passive"))
      (node (ref "R4") (pin "2") (pinfunction "P$2_2") (pintype "passive"))
      (node (ref "R6") (pin "1") (pinfunction "P$1_1") (pintype "passive"))
      (node (ref "R6") (pin "2") (pinfunction "P$2_2") (pintype "passive"))
      (node (ref "R8") (pin "2") (pinfunction "P$2_2") (pintype "passive"))
      (node (ref "SW1") (pin "C") (pinfunction "C_C") (pintype "bidirectional"))
      (node (ref "SW2") (pin "C") (pinfunction "C_C") (pintype "bidirectional"))
      (node (ref "SW3") (pin "C") (pinfunction "C_C") (pintype "bidirectional"))
      (node (ref "U1") (pin "4") (pinfunction "GND_2_4") (pintype "passive"))
      (node (ref "U1") (pin "5") (pinfunction "GND_5") (pintype "passive"))
      (node (ref "U2") (pin "1") (pinfunction "VSS_1") (pintype "power_in"))
      (node (ref "U2") (pin "16") (pinfunction "K_16") (pintype "power_in"))
      (node (ref "U2") (pin "5") (pinfunction "R/W_5") (pintype "input"))
    )
    (net (code "17") (name "MISO") (class "Default")
      (node (ref "ARDUINO") (pin "15") (pinfunction "12_15") (pintype "bidirectional"))
      (node (ref "U2") (pin "4") (pinfunction "RS_4") (pintype "input"))
    )
    (net (code "18") (name "MOSI") (class "Default")
      (node (ref "ARDUINO") (pin "14") (pinfunction "*11_14") (pintype "bidirectional"))
      (node (ref "U2") (pin "6") (pinfunction "E_6") (pintype "input"))
    )
    (net (code "19") (name "N$5") (class "Default")
      (node (ref "R13") (pin "2") (pinfunction "P$2_2") (pintype "passive"))
      (node (ref "R17") (pin "2") (pinfunction "P$2_2") (pintype "passive"))
      (node (ref "R21") (pin "2") (pinfunction "P$2_2") (pintype "passive"))
      (node (ref "R25") (pin "2") (pinfunction "P$2_2") (pintype "passive"))
      (node (ref "R29") (pin "2") (pinfunction "P$2_2") (pintype "passive"))
      (node (ref "R33") (pin "2") (pinfunction "P$2_2") (pintype "passive"))
      (node (ref "R5") (pin "2") (pinfunction "P$2_2") (pintype "passive"))
      (node (ref "R9") (pin "2") (pinfunction "P$2_2") (pintype "passive"))
    )
    (net (code "20") (name "Net-(Q2-G)") (class "Default")
      (node (ref "Q2") (pin "1") (pinfunction "G_1") (pintype "passive"))
      (node (ref "R3") (pin "2") (pinfunction "P$2_2") (pintype "passive"))
      (node (ref "R5") (pin "1") (pinfunction "P$1_1") (pintype "passive"))
    )
    (net (code "21") (name "Net-(Q4-G)") (class "Default")
      (node (ref "Q4") (pin "1") (pinfunction "G_1") (pintype "passive"))
      (node (ref "R7") (pin "2") (pinfunction "P$2_2") (pintype "passive"))
      (node (ref "R9") (pin "1") (pinfunction "P$1_1") (pintype "passive"))
    )
    (net (code "22") (name "Net-(Q6-G)") (class "Default")
      (node (ref "Q6") (pin "1") (pinfunction "G_1") (pintype "passive"))
      (node (ref "R11") (pin "2") (pinfunction "P$2_2") (pintype "passive"))
      (node (ref "R13") (pin "1") (pinfunction "P$1_1") (pintype "passive"))
    )
    (net (code "23") (name "Net-(Q8-G)") (class "Default")
      (node (ref "Q8") (pin "1") (pinfunction "G_1") (pintype "passive"))
      (node (ref "R15") (pin "2") (pinfunction "P$2_2") (pintype "passive"))
      (node (ref "R17") (pin "1") (pinfunction "P$1_1") (pintype "passive"))
    )
    (net (code "24") (name "Net-(Q10-G)") (class "Default")
      (node (ref "Q10") (pin "1") (pinfunction "G_1") (pintype "passive"))
      (node (ref "R19") (pin "2") (pinfunction "P$2_2") (pintype "passive"))
      (node (ref "R21") (pin "1") (pinfunction "P$1_1") (pintype "passive"))
    )
    (net (code "25") (name "Net-(Q12-G)") (class "Default")
      (node (ref "Q12") (pin "1") (pinfunction "G_1") (pintype "passive"))
      (node (ref "R23") (pin "2") (pinfunction "P$2_2") (pintype "passive"))
      (node (ref "R25") (pin "1") (pinfunction "P$1_1") (pintype "passive"))
    )
    (net (code "26") (name "Net-(Q14-G)") (class "Default")
      (node (ref "Q14") (pin "1") (pinfunction "G_1") (pintype "passive"))
      (node (ref "R27") (pin "2") (pinfunction "P$2_2") (pintype "passive"))
      (node (ref "R29") (pin "1") (pinfunction "P$1_1") (pintype "passive"))
    )
    (net (code "27") (name "Net-(Q16-G)") (class "Default")
      (node (ref "Q16") (pin "1") (pinfunction "G_1") (pintype "passive"))
      (node (ref "R31") (pin "2") (pinfunction "P$2_2") (pintype "passive"))
      (node (ref "R33") (pin "1") (pinfunction "P$1_1") (pintype "passive"))
    )
    (net (code "28") (name "Net-(R1-P$2)") (class "Default")
      (node (ref "R1") (pin "2") (pinfunction "P$2_2") (pintype "passive"))
      (node (ref "R2") (pin "1") (pinfunction "P$1_1") (pintype "passive"))
      (node (ref "U1") (pin "2") (pinfunction "IN_2") (pintype "input"))
    )
    (net (code "29") (name "Net-(R35-P$2)") (class "Default")
      (node (ref "R35") (pin "2") (pinfunction "P$2_2") (pintype "passive"))
      (node (ref "R36") (pin "1") (pinfunction "P$1_1") (pintype "passive"))
      (node (ref "U2") (pin "3") (pinfunction "VO_3") (pintype "bidirectional"))
    )
    (net (code "30") (name "Net-(R37-P$1)") (class "Default")
      (node (ref "R37") (pin "1") (pinfunction "P$1_1") (pintype "passive"))
      (node (ref "U2") (pin "15") (pinfunction "A_15") (pintype "power_in"))
    )
    (net (code "31") (name "Net-(U1-VDD)") (class "Default")
      (node (ref "C1") (pin "1") (pinfunction "1_1") (pintype "passive"))
      (node (ref "C2") (pin "1") (pinfunction "1_1") (pintype "passive"))
      (node (ref "C3") (pin "1") (pinfunction "1_1") (pintype "passive"))
      (node (ref "U1") (pin "1") (pinfunction "VDD_1") (pintype "power_in"))
      (node (ref "U1") (pin "8") (pinfunction "VDD_2_8") (pintype "power_in"))
    )
    (net (code "32") (name "SW") (class "Default")
      (node (ref "ARDUINO") (pin "11") (pinfunction "8_11") (pintype "bidirectional"))
    )
    (net (code "33") (name "TRIG") (class "Default")
      (node (ref "C4") (pin "2") (pinfunction "2_2") (pintype "passive"))
      (node (ref "C5") (pin "1") (pinfunction "1_1") (pintype "passive"))
      (node (ref "J1") (pin "1") (pinfunction "1_1") (pintype "passive"))
      (node (ref "J10") (pin "1") (pinfunction "1_1") (pintype "passive"))
      (node (ref "J11") (pin "1") (pinfunction "1_1") (pintype "passive"))
      (node (ref "J12") (pin "1") (pinfunction "1_1") (pintype "passive"))
      (node (ref "J13") (pin "1") (pinfunction "1_1") (pintype "passive"))
      (node (ref "J14") (pin "1") (pinfunction "1_1") (pintype "passive"))
      (node (ref "J15") (pin "1") (pinfunction "1_1") (pintype "passive"))
      (node (ref "J16") (pin "1") (pinfunction "1_1") (pintype "passive"))
      (node (ref "J2") (pin "1") (pinfunction "1_1") (pintype "passive"))
      (node (ref "J3") (pin "1") (pinfunction "1_1") (pintype "passive"))
      (node (ref "J4") (pin "1") (pinfunction "1_1") (pintype "passive"))
      (node (ref "J5") (pin "1") (pinfunction "1_1") (pintype "passive"))
      (node (ref "J6") (pin "1") (pinfunction "1_1") (pintype "passive"))
      (node (ref "J7") (pin "1") (pinfunction "1_1") (pintype "passive"))
      (node (ref "J8") (pin "1") (pinfunction "1_1") (pintype "passive"))
      (node (ref "J9") (pin "1") (pinfunction "1_1") (pintype "passive"))
      (node (ref "R11") (pin "1") (pinfunction "P$1_1") (pintype "passive"))
      (node (ref "R12") (pin "1") (pinfunction "P$1_1") (pintype "passive"))
      (node (ref "R15") (pin "1") (pinfunction "P$1_1") (pintype "passive"))
      (node (ref "R16") (pin "1") (pinfunction "P$1_1") (pintype "passive"))
      (node (ref "R19") (pin "1") (pinfunction "P$1_1") (pintype "passive"))
      (node (ref "R20") (pin "1") (pinfunction "P$1_1") (pintype "passive"))
      (node (ref "R23") (pin "1") (pinfunction "P$1_1") (pintype "passive"))
      (node (ref "R24") (pin "1") (pinfunction "P$1_1") (pintype "passive"))
      (node (ref "R27") (pin "1") (pinfunction "P$1_1") (pintype "passive"))
      (node (ref "R28") (pin "1") (pinfunction "P$1_1") (pintype "passive"))
      (node (ref "R3") (pin "1") (pinfunction "P$1_1") (pintype "passive"))
      (node (ref "R31") (pin "1") (pinfunction "P$1_1") (pintype "passive"))
      (node (ref "R32") (pin "1") (pinfunction "P$1_1") (pintype "passive"))
      (node (ref "R4") (pin "1") (pinfunction "P$1_1") (pintype "passive"))
      (node (ref "R7") (pin "1") (pinfunction "P$1_1") (pintype "passive"))
      (node (ref "R8") (pin "1") (pinfunction "P$1_1") (pintype "passive"))
      (node (ref "U1") (pin "6") (pinfunction "*OUT_2_6") (pintype "output"))
      (node (ref "U1") (pin "7") (pinfunction "*OUT_7") (pintype "output"))
    )
    (net (code "34") (name "TRIG_5V") (class "Default")
      (node (ref "ARDUINO") (pin "12") (pinfunction "*9_12") (pintype "bidirectional"))
      (node (ref "R2") (pin "2") (pinfunction "P$2_2") (pintype "passive"))
    )
    (net (code "35") (name "unconnected-(ARDUINO-A1-Pad18)") (class "Default")
      (node (ref "ARDUINO") (pin "18") (pinfunction "A1_18") (pintype "bidirectional"))
    )
    (net (code "36") (name "unconnected-(ARDUINO-A2-Pad19)") (class "Default")
      (node (ref "ARDUINO") (pin "19") (pinfunction "A2_19") (pintype "bidirectional"))
    )
    (net (code "37") (name "unconnected-(ARDUINO-A3-Pad20)") (class "Default")
      (node (ref "ARDUINO") (pin "20") (pinfunction "A3_20") (pintype "bidirectional"))
    )
    (net (code "38") (name "unconnected-(ARDUINO-GND-Pad4)") (class "Default")
      (node (ref "ARDUINO") (pin "4") (pinfunction "GND_4") (pintype "bidirectional"))
    )
    (net (code "39") (name "unconnected-(ARDUINO-PadA4)") (class "Default")
      (node (ref "ARDUINO") (pin "A4") (pinfunction "A4_A4") (pintype "bidirectional"))
    )
    (net (code "40") (name "unconnected-(ARDUINO-PadA5)") (class "Default")
      (node (ref "ARDUINO") (pin "A5") (pinfunction "A5_A5") (pintype "bidirectional"))
    )
    (net (code "41") (name "unconnected-(ARDUINO-PadA6)") (class "Default")
      (node (ref "ARDUINO") (pin "A6") (pinfunction "A6_A6") (pintype "bidirectional"))
    )
    (net (code "42") (name "unconnected-(ARDUINO-PadA7)") (class "Default")
      (node (ref "ARDUINO") (pin "A7") (pinfunction "A7_A7") (pintype "bidirectional"))
    )
    (net (code "43") (name "unconnected-(ARDUINO-RST-Pad3)") (class "Default")
      (node (ref "ARDUINO") (pin "3") (pinfunction "RST_3") (pintype "bidirectional"))
    )
    (net (code "44") (name "unconnected-(ARDUINO-RST-Pad22)") (class "Default")
      (node (ref "ARDUINO") (pin "22") (pinfunction "RST_22") (pintype "bidirectional"))
    )
    (net (code "45") (name "unconnected-(ARDUINO-RXI-Pad2)") (class "Default")
      (node (ref "ARDUINO") (pin "2") (pinfunction "RXI_2") (pintype "bidirectional"))
    )
    (net (code "46") (name "unconnected-(ARDUINO-TXO-Pad1)") (class "Default")
      (node (ref "ARDUINO") (pin "1") (pinfunction "TXO_1") (pintype "bidirectional"))
    )
    (net (code "47") (name "unconnected-(U1-NC-Pad3)") (class "Default")
      (node (ref "U1") (pin "3") (pinfunction "NC_3") (pintype "no_connect"))
    )
    (net (code "48") (name "unconnected-(U2-DB0-Pad7)") (class "Default")
      (node (ref "U2") (pin "7") (pinfunction "DB0_7") (pintype "bidirectional"))
    )
    (net (code "49") (name "unconnected-(U2-DB1-Pad8)") (class "Default")
      (node (ref "U2") (pin "8") (pinfunction "DB1_8") (pintype "bidirectional"))
    )
    (net (code "50") (name "unconnected-(U2-DB2-Pad9)") (class "Default")
      (node (ref "U2") (pin "9") (pinfunction "DB2_9") (pintype "bidirectional"))
    )
    (net (code "51") (name "unconnected-(U2-DB3-Pad10)") (class "Default")
      (node (ref "U2") (pin "10") (pinfunction "DB3_10") (pintype "bidirectional"))
    )
  )
)
